# Development.net
KiCad netlist of a schematic drawn in EAGLE
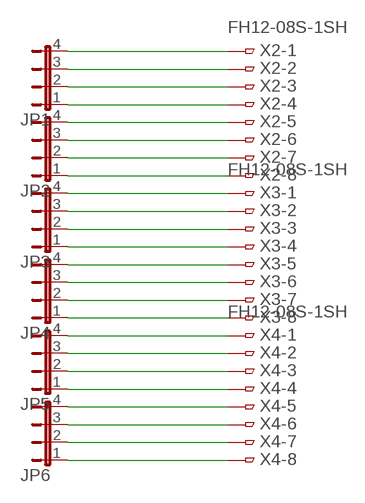
[diagram p0: schematic, sheet 1]

(export (version "E")
  (design (tool "Eeschema 10.0.6"))
  (components
    (comp (ref "JP1")
      (value "JP4E")
      (footprint "eagle-import:JP4")
      (libsource (lib "eagle-import") (part "JP4E"))
    )
    (comp (ref "JP2")
      (value "JP4E")
      (footprint "eagle-import:JP4")
      (libsource (lib "eagle-import") (part "JP4E"))
    )
    (comp (ref "JP3")
      (value "JP4E")
      (footprint "eagle-import:JP4")
      (libsource (lib "eagle-import") (part "JP4E"))
    )
    (comp (ref "JP4")
      (value "JP4E")
      (footprint "eagle-import:JP4")
      (libsource (lib "eagle-import") (part "JP4E"))
    )
    (comp (ref "JP5")
      (value "JP4E")
      (footprint "eagle-import:JP4")
      (libsource (lib "eagle-import") (part "JP4E"))
    )
    (comp (ref "JP6")
      (value "JP4E")
      (footprint "eagle-import:JP4")
      (libsource (lib "eagle-import") (part "JP4E"))
    )
    (comp (ref "X2")
      (value "FH12-08S-1SH")
      (footprint "eagle-import:FH12-08S-1SH")
      (libsource (lib "eagle-import") (part "FH12-08S-1SH"))
    )
    (comp (ref "X3")
      (value "FH12-08S-1SH")
      (footprint "eagle-import:FH12-08S-1SH")
      (libsource (lib "eagle-import") (part "FH12-08S-1SH"))
    )
    (comp (ref "X4")
      (value "FH12-08S-1SH")
      (footprint "eagle-import:FH12-08S-1SH")
      (libsource (lib "eagle-import") (part "FH12-08S-1SH"))
    )
  )
  (nets
    (net (code "1") (name "Net-(JP1-Pad4)") (class "Default")
      (node (ref "JP1") (pin "4") (pinfunction "4_4") (pintype "passive"))
      (node (ref "X2") (pin "1") (pinfunction "1_1") (pintype "passive"))
    )
    (net (code "2") (name "Net-(JP3-Pad4)") (class "Default")
      (node (ref "JP3") (pin "4") (pinfunction "4_4") (pintype "passive"))
      (node (ref "X3") (pin "1") (pinfunction "1_1") (pintype "passive"))
    )
    (net (code "3") (name "Net-(JP5-Pad4)") (class "Default")
      (node (ref "JP5") (pin "4") (pinfunction "4_4") (pintype "passive"))
      (node (ref "X4") (pin "1") (pinfunction "1_1") (pintype "passive"))
    )
    (net (code "4") (name "Net-(X2B-1)") (class "Default")
      (node (ref "JP1") (pin "3") (pinfunction "3_3") (pintype "passive"))
      (node (ref "X2") (pin "2") (pinfunction "1_2") (pintype "passive"))
    )
    (net (code "5") (name "Net-(X2C-1)") (class "Default")
      (node (ref "JP1") (pin "2") (pinfunction "2_2") (pintype "passive"))
      (node (ref "X2") (pin "3") (pinfunction "1_3") (pintype "passive"))
    )
    (net (code "6") (name "Net-(X2D-1)") (class "Default")
      (node (ref "JP1") (pin "1") (pinfunction "1_1") (pintype "passive"))
      (node (ref "X2") (pin "4") (pinfunction "1_4") (pintype "passive"))
    )
    (net (code "7") (name "Net-(X2E-1)") (class "Default")
      (node (ref "JP2") (pin "4") (pinfunction "4_4") (pintype "passive"))
      (node (ref "X2") (pin "5") (pinfunction "1_5") (pintype "passive"))
    )
    (net (code "8") (name "Net-(X2F-1)") (class "Default")
      (node (ref "JP2") (pin "3") (pinfunction "3_3") (pintype "passive"))
      (node (ref "X2") (pin "6") (pinfunction "1_6") (pintype "passive"))
    )
    (net (code "9") (name "Net-(X2G-1)") (class "Default")
      (node (ref "JP2") (pin "2") (pinfunction "2_2") (pintype "passive"))
      (node (ref "X2") (pin "7") (pinfunction "1_7") (pintype "passive"))
    )
    (net (code "10") (name "Net-(X2H-1)") (class "Default")
      (node (ref "JP2") (pin "1") (pinfunction "1_1") (pintype "passive"))
      (node (ref "X2") (pin "8") (pinfunction "1_8") (pintype "passive"))
    )
    (net (code "11") (name "Net-(X3B-1)") (class "Default")
      (node (ref "JP3") (pin "3") (pinfunction "3_3") (pintype "passive"))
      (node (ref "X3") (pin "2") (pinfunction "1_2") (pintype "passive"))
    )
    (net (code "12") (name "Net-(X3C-1)") (class "Default")
      (node (ref "JP3") (pin "2") (pinfunction "2_2") (pintype "passive"))
      (node (ref "X3") (pin "3") (pinfunction "1_3") (pintype "passive"))
    )
    (net (code "13") (name "Net-(X3D-1)") (class "Default")
      (node (ref "JP3") (pin "1") (pinfunction "1_1") (pintype "passive"))
      (node (ref "X3") (pin "4") (pinfunction "1_4") (pintype "passive"))
    )
    (net (code "14") (name "Net-(X3E-1)") (class "Default")
      (node (ref "JP4") (pin "4") (pinfunction "4_4") (pintype "passive"))
      (node (ref "X3") (pin "5") (pinfunction "1_5") (pintype "passive"))
    )
    (net (code "15") (name "Net-(X3F-1)") (class "Default")
      (node (ref "JP4") (pin "3") (pinfunction "3_3") (pintype "passive"))
      (node (ref "X3") (pin "6") (pinfunction "1_6") (pintype "passive"))
    )
    (net (code "16") (name "Net-(X3G-1)") (class "Default")
      (node (ref "JP4") (pin "2") (pinfunction "2_2") (pintype "passive"))
      (node (ref "X3") (pin "7") (pinfunction "1_7") (pintype "passive"))
    )
    (net (code "17") (name "Net-(X3H-1)") (class "Default")
      (node (ref "JP4") (pin "1") (pinfunction "1_1") (pintype "passive"))
      (node (ref "X3") (pin "8") (pinfunction "1_8") (pintype "passive"))
    )
    (net (code "18") (name "Net-(X4B-1)") (class "Default")
      (node (ref "JP5") (pin "3") (pinfunction "3_3") (pintype "passive"))
      (node (ref "X4") (pin "2") (pinfunction "1_2") (pintype "passive"))
    )
    (net (code "19") (name "Net-(X4C-1)") (class "Default")
      (node (ref "JP5") (pin "2") (pinfunction "2_2") (pintype "passive"))
      (node (ref "X4") (pin "3") (pinfunction "1_3") (pintype "passive"))
    )
    (net (code "20") (name "Net-(X4D-1)") (class "Default")
      (node (ref "JP5") (pin "1") (pinfunction "1_1") (pintype "passive"))
      (node (ref "X4") (pin "4") (pinfunction "1_4") (pintype "passive"))
    )
    (net (code "21") (name "Net-(X4E-1)") (class "Default")
      (node (ref "JP6") (pin "4") (pinfunction "4_4") (pintype "passive"))
      (node (ref "X4") (pin "5") (pinfunction "1_5") (pintype "passive"))
    )
    (net (code "22") (name "Net-(X4F-1)") (class "Default")
      (node (ref "JP6") (pin "3") (pinfunction "3_3") (pintype "passive"))
      (node (ref "X4") (pin "6") (pinfunction "1_6") (pintype "passive"))
    )
    (net (code "23") (name "Net-(X4G-1)") (class "Default")
      (node (ref "JP6") (pin "2") (pinfunction "2_2") (pintype "passive"))
      (node (ref "X4") (pin "7") (pinfunction "1_7") (pintype "passive"))
    )
    (net (code "24") (name "Net-(X4H-1)") (class "Default")
      (node (ref "JP6") (pin "1") (pinfunction "1_1") (pintype "passive"))
      (node (ref "X4") (pin "8") (pinfunction "1_8") (pintype "passive"))
    )
  )
)
